# braids_v50.net
KiCad netlist of a schematic drawn in EAGLE
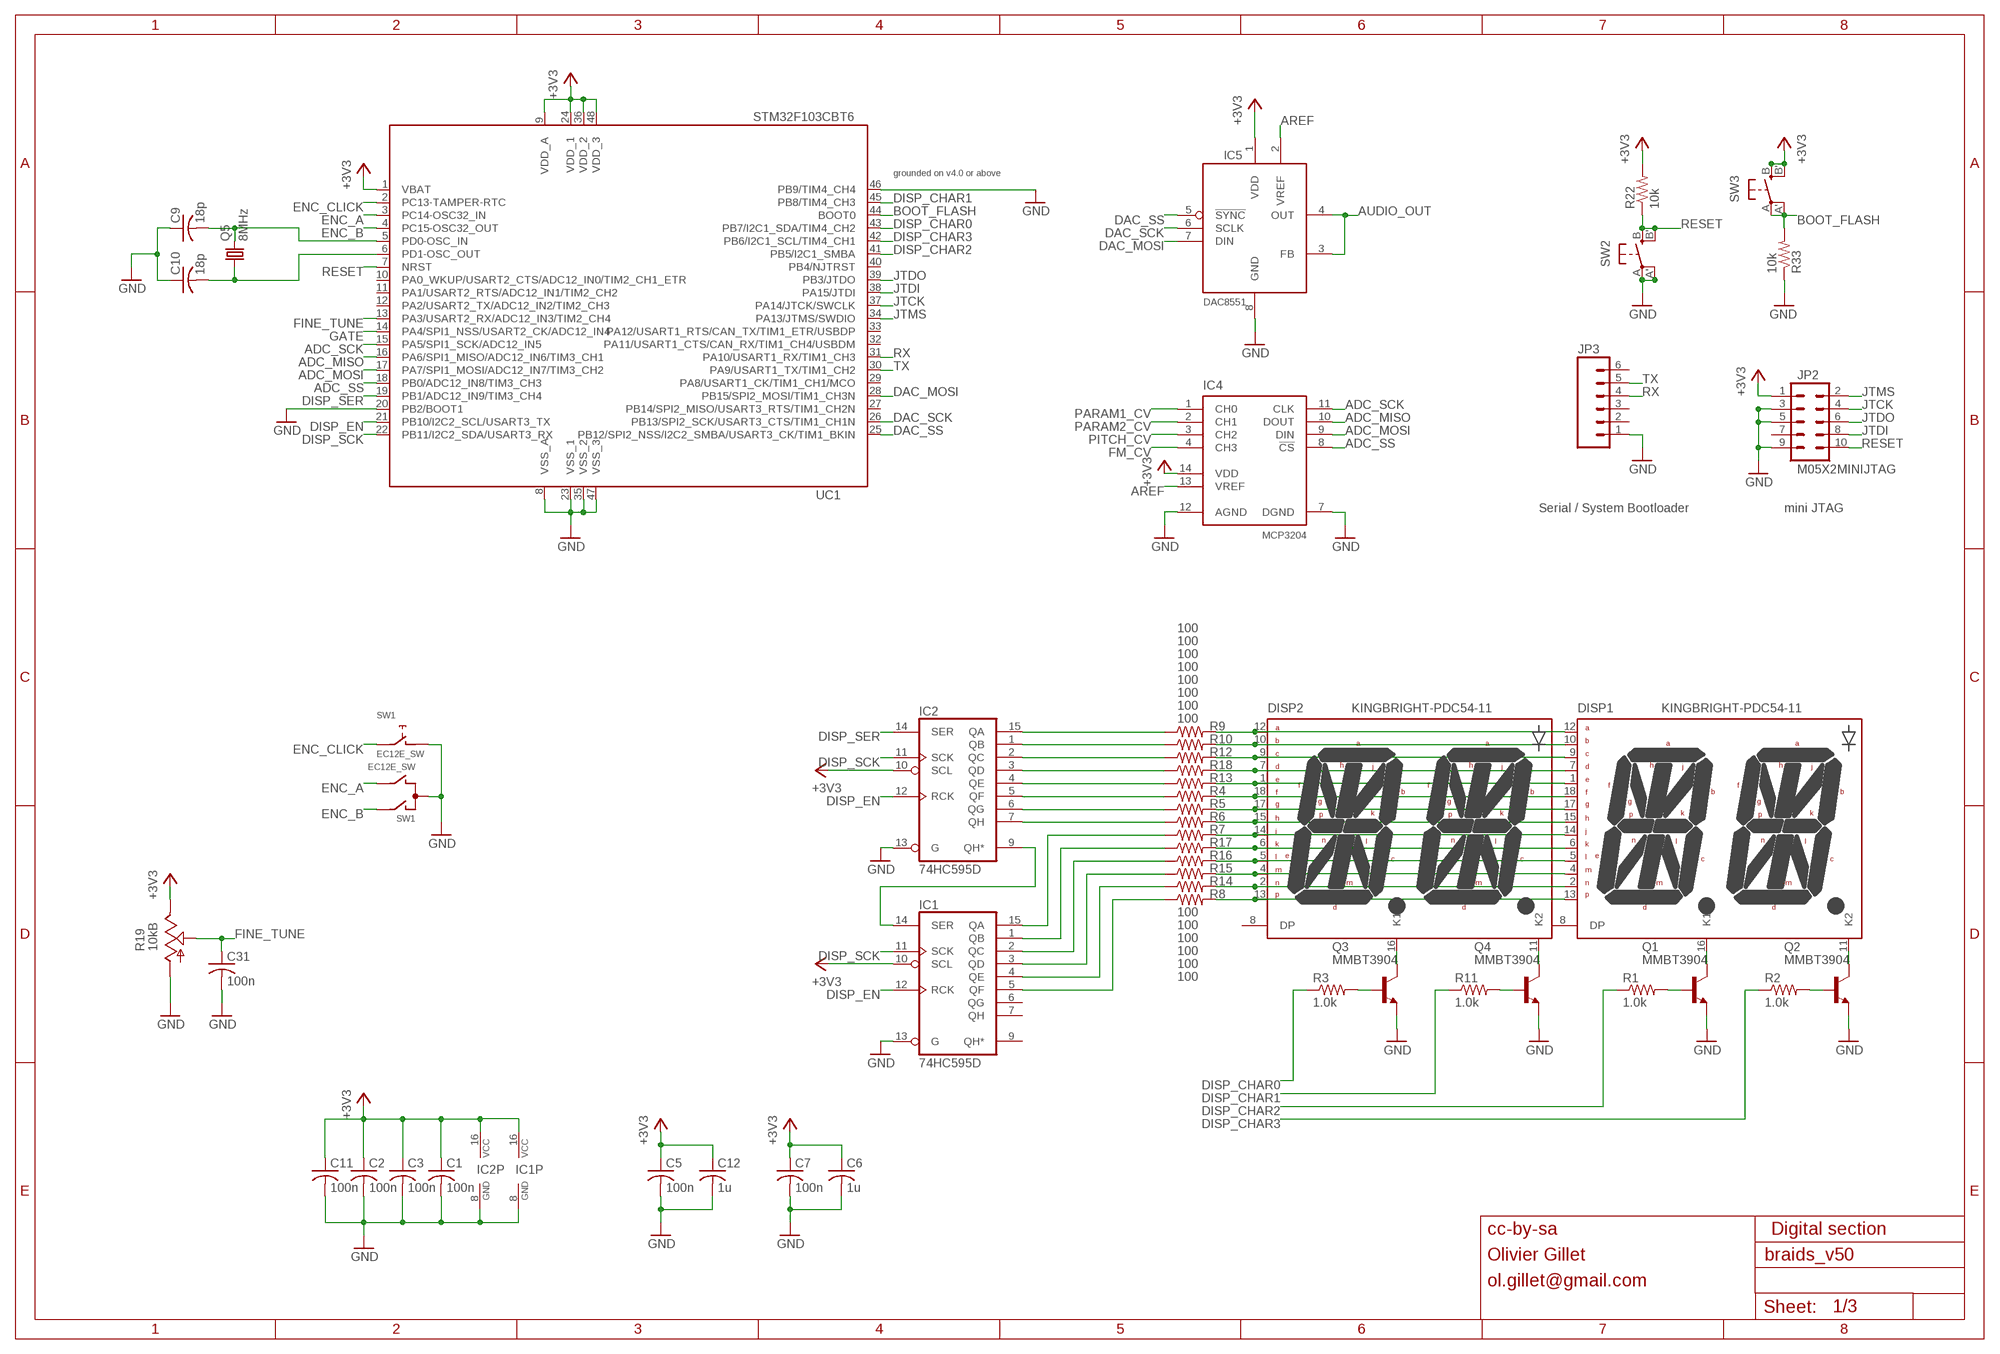
[diagram p0: schematic, sheet 1]
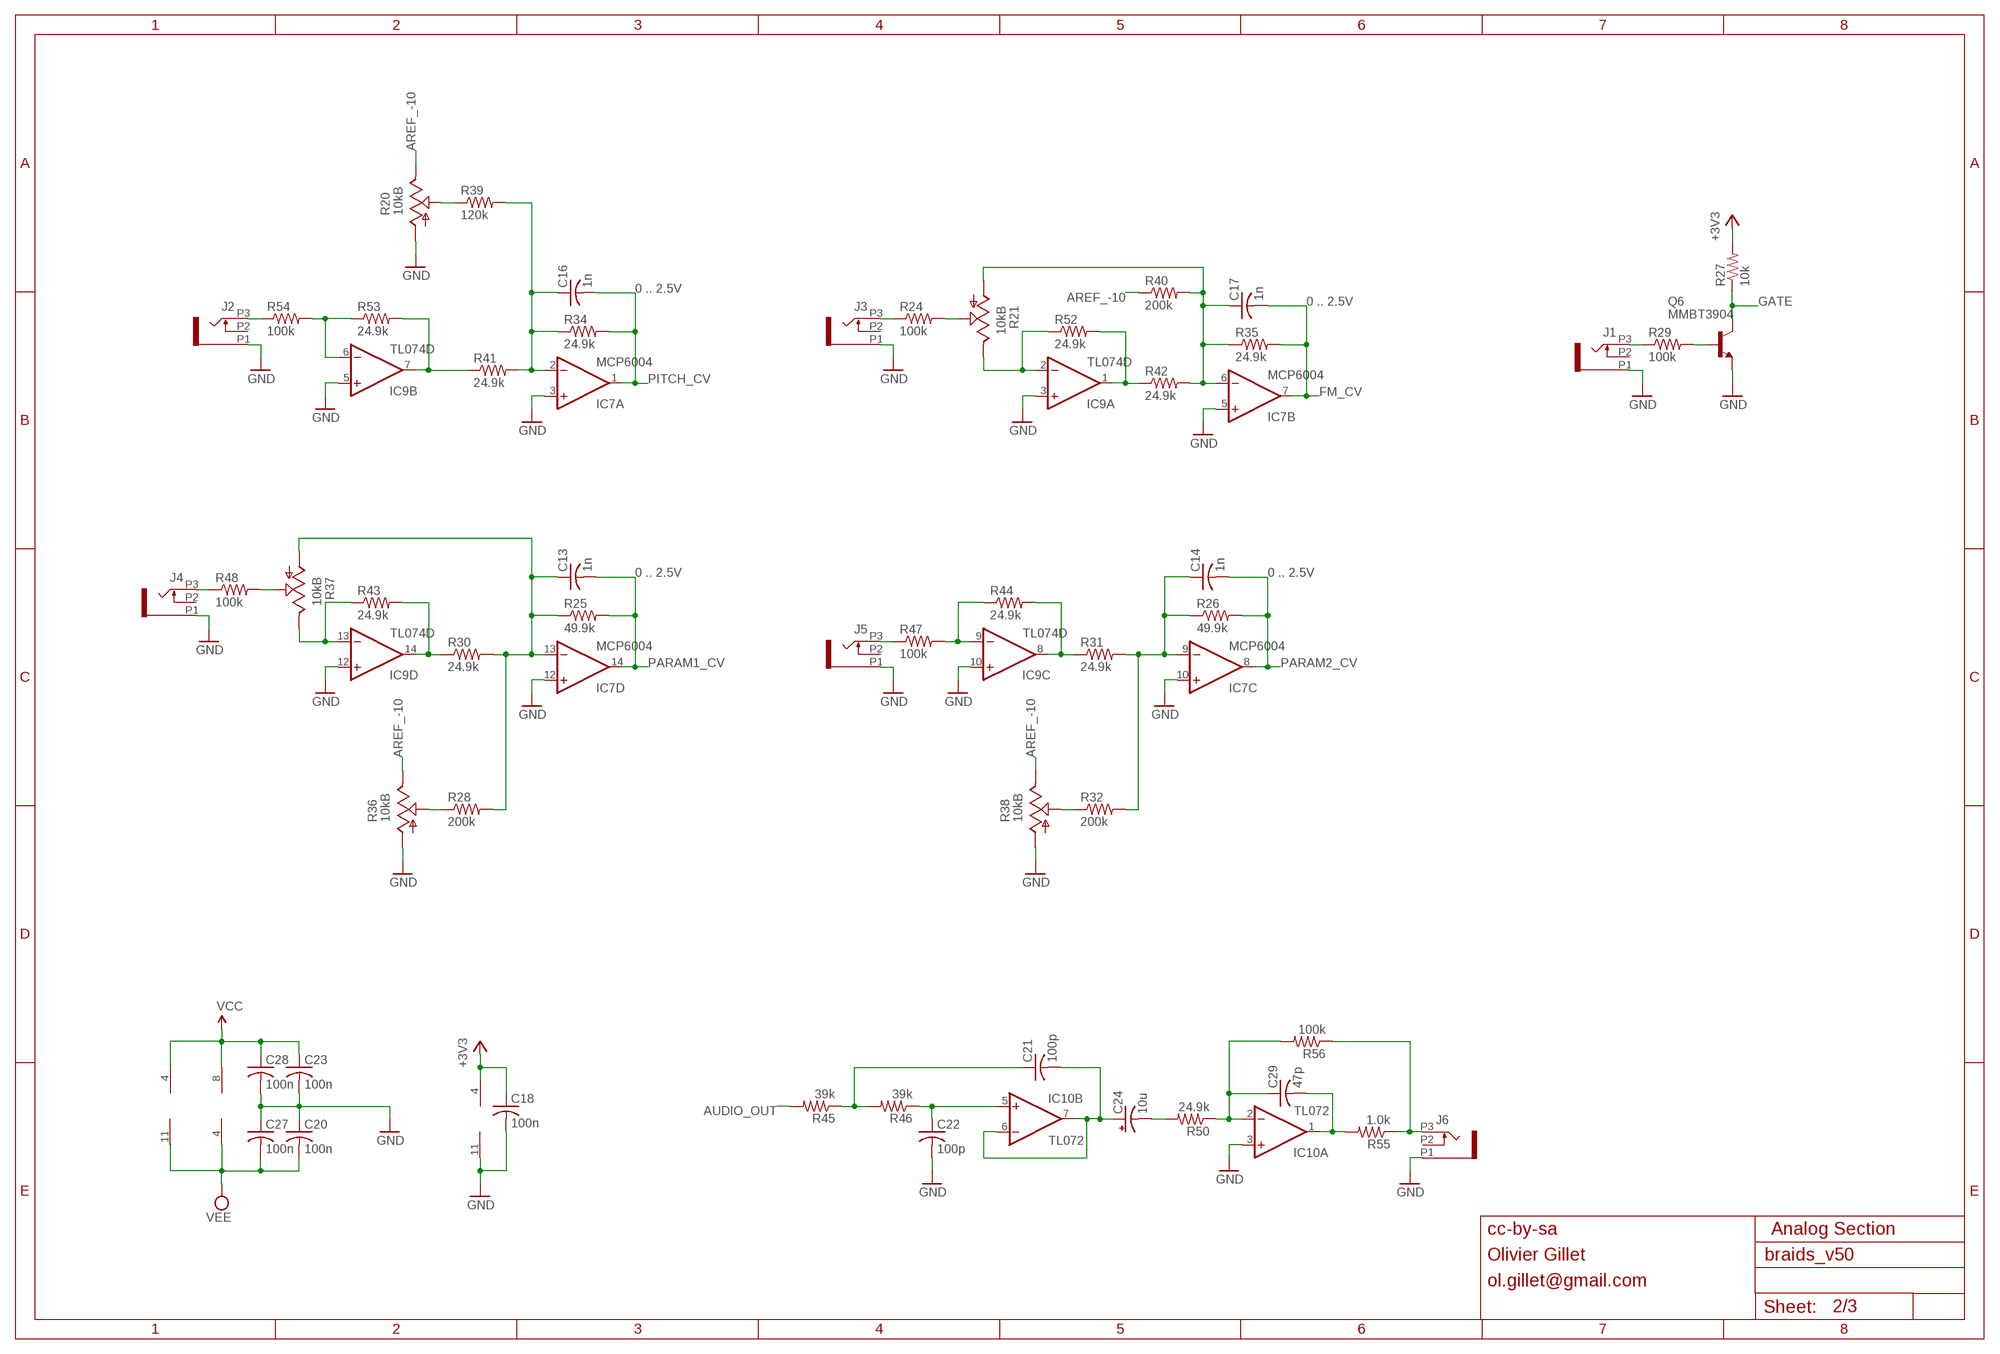
[diagram p1: schematic, sheet 2]
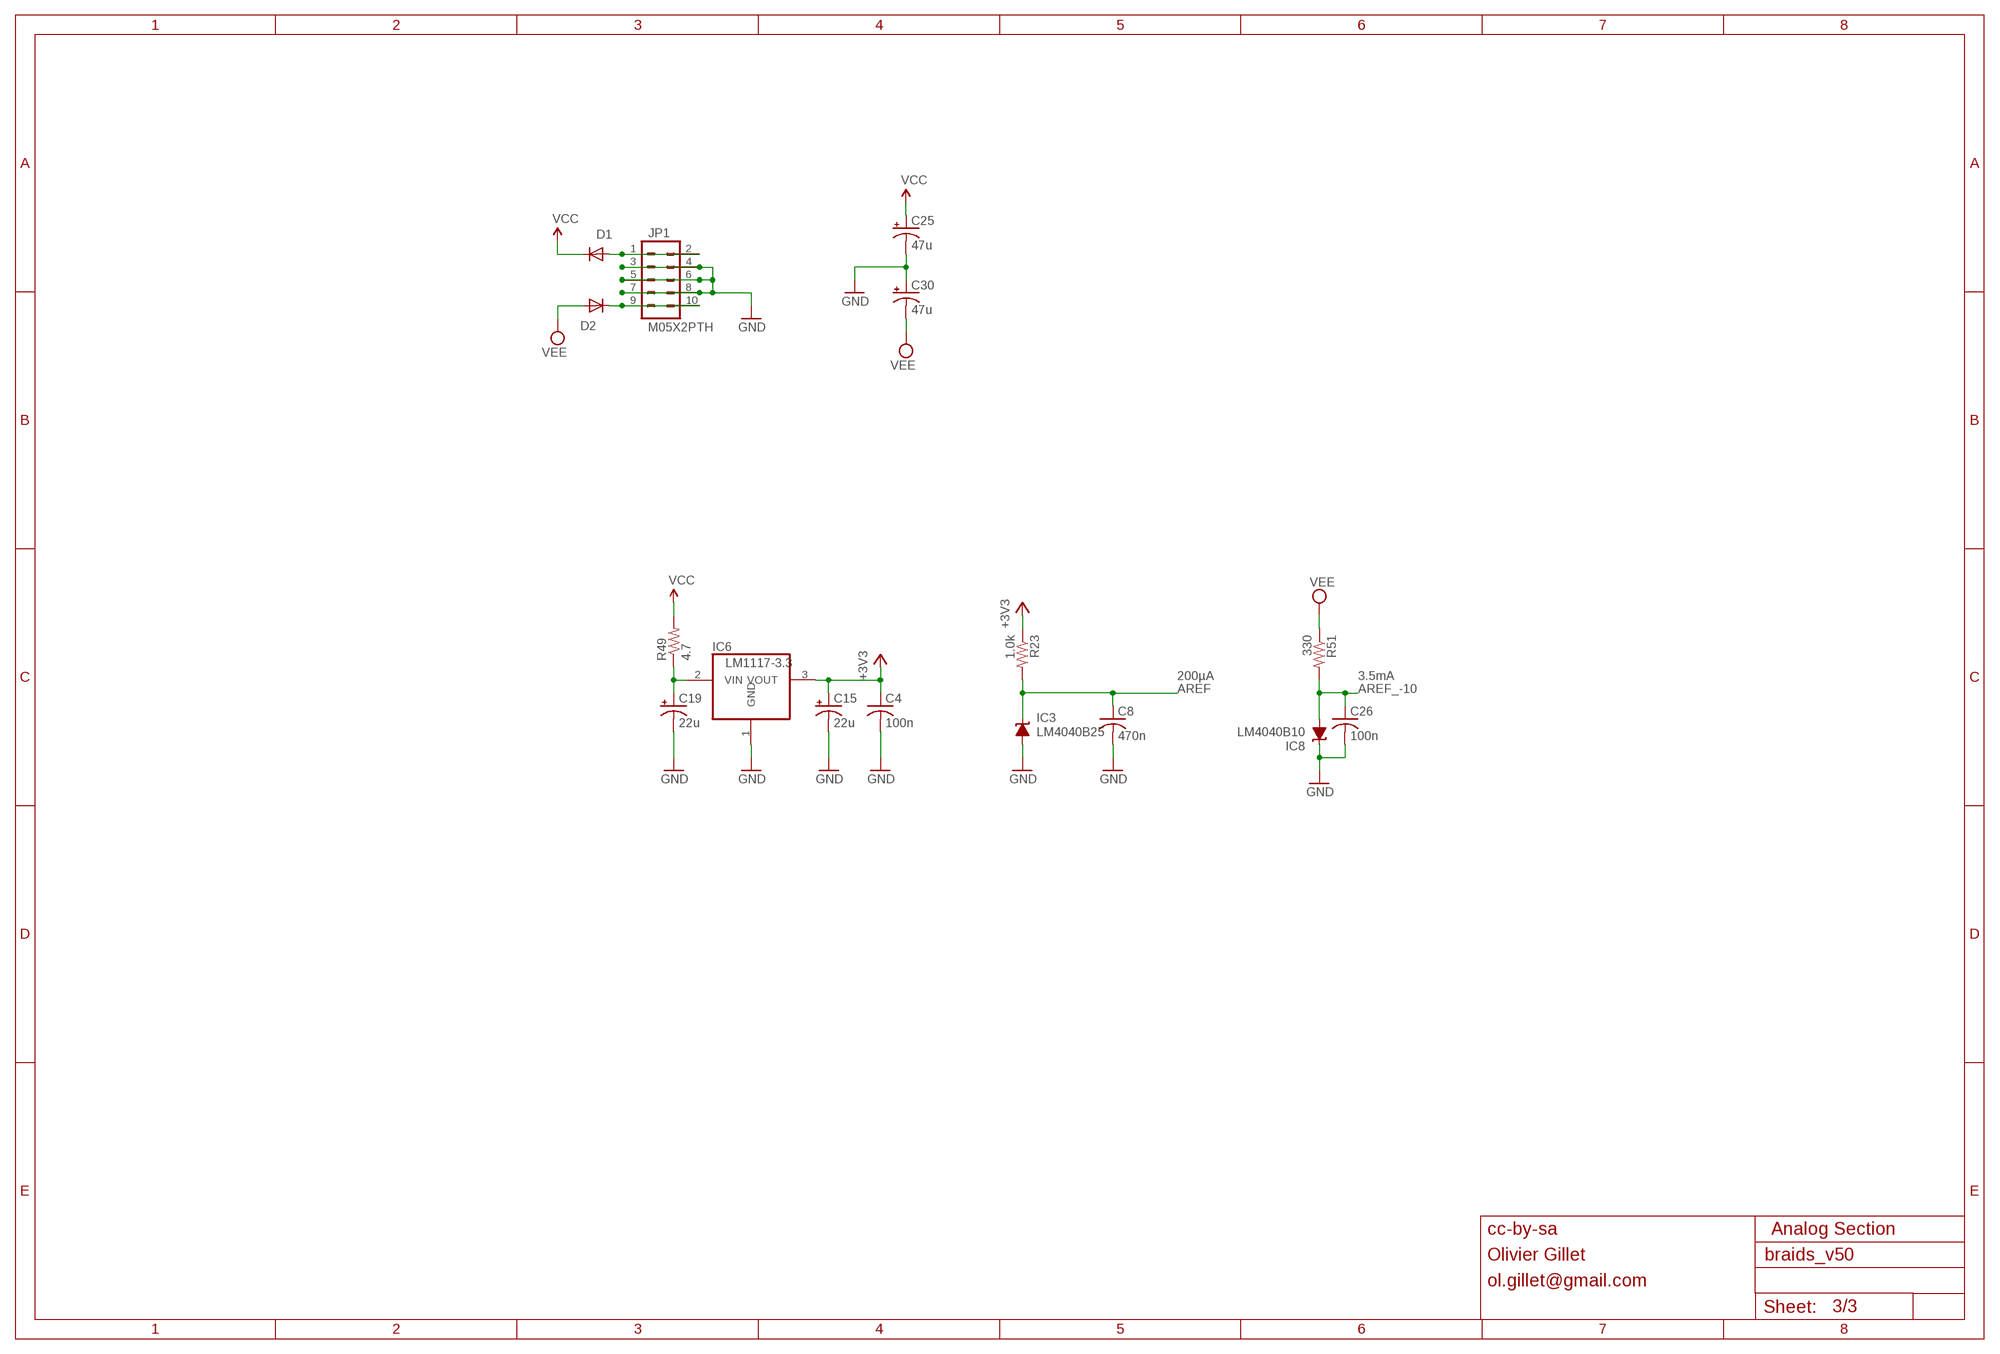
[diagram p2: schematic, sheet 3]

(export (version "E")
  (design (tool "Eeschema 10.0.6"))
  (components
    (comp (ref "C4")
      (value "100n")
      (footprint "eagle-import:C0603")
      (libsource (lib "eagle-import") (part "C-USC0603"))
    )
    (comp (ref "C8")
      (value "470n")
      (footprint "eagle-import:C0603")
      (libsource (lib "eagle-import") (part "C-USC0603"))
    )
    (comp (ref "C15")
      (value "22u")
      (footprint "eagle-import:PANASONIC_C")
      (libsource (lib "eagle-import") (part "CPOL-USC"))
    )
    (comp (ref "C19")
      (value "22u")
      (footprint "eagle-import:PANASONIC_C")
      (libsource (lib "eagle-import") (part "CPOL-USC"))
    )
    (comp (ref "C25")
      (value "47u")
      (footprint "eagle-import:PANASONIC_D")
      (libsource (lib "eagle-import") (part "CPOL-USD"))
    )
    (comp (ref "C26")
      (value "100n")
      (footprint "eagle-import:C0603")
      (libsource (lib "eagle-import") (part "C-USC0603"))
    )
    (comp (ref "C30")
      (value "47u")
      (footprint "eagle-import:PANASONIC_D")
      (libsource (lib "eagle-import") (part "CPOL-USD"))
    )
    (comp (ref "D1")
      (value "1N5819HW")
      (footprint "eagle-import:SOD123")
      (libsource (lib "eagle-import") (part "DIODE-SOD123"))
    )
    (comp (ref "D2")
      (value "1N5819HW")
      (footprint "eagle-import:SOD123")
      (libsource (lib "eagle-import") (part "DIODE-SOD123"))
    )
    (comp (ref "IC3")
      (value "LM4040B25")
      (footprint "eagle-import:DBZ_R-PDSO-G3")
      (libsource (lib "eagle-import") (part "LM4041DBZB12"))
    )
    (comp (ref "IC6")
      (value "LM1117-3.3")
      (footprint "eagle-import:TO252")
      (libsource (lib "eagle-import") (part "REG1117T"))
    )
    (comp (ref "IC8")
      (value "LM4040B10")
      (footprint "eagle-import:DBZ_R-PDSO-G3")
      (libsource (lib "eagle-import") (part "LM4041DBZB12"))
    )
    (comp (ref "JP1")
      (value "M05X2PTH")
      (footprint "eagle-import:AVR_ICSP")
      (libsource (lib "eagle-import") (part "M05X2PTH"))
    )
    (comp (ref "R23")
      (value "1.0k")
      (footprint "eagle-import:R0603")
      (libsource (lib "eagle-import") (part "R-US_R0603"))
    )
    (comp (ref "R49")
      (value "4.7")
      (footprint "eagle-import:R1206")
      (libsource (lib "eagle-import") (part "R-US_R1206"))
    )
    (comp (ref "R51")
      (value "330")
      (footprint "eagle-import:R0603")
      (libsource (lib "eagle-import") (part "R-US_R0603"))
    )
    (comp (ref "C13")
      (value "1n")
      (footprint "eagle-import:C0603")
      (libsource (lib "eagle-import") (part "C-USC0603"))
    )
    (comp (ref "C14")
      (value "1n")
      (footprint "eagle-import:C0603")
      (libsource (lib "eagle-import") (part "C-USC0603"))
    )
    (comp (ref "C16")
      (value "1n")
      (footprint "eagle-import:C0603")
      (libsource (lib "eagle-import") (part "C-USC0603"))
    )
    (comp (ref "C17")
      (value "1n")
      (footprint "eagle-import:C0603")
      (libsource (lib "eagle-import") (part "C-USC0603"))
    )
    (comp (ref "C18")
      (value "100n")
      (footprint "eagle-import:C0603")
      (libsource (lib "eagle-import") (part "C-USC0603"))
    )
    (comp (ref "C20")
      (value "100n")
      (footprint "eagle-import:C0603")
      (libsource (lib "eagle-import") (part "C-USC0603"))
    )
    (comp (ref "C21")
      (value "100p")
      (footprint "eagle-import:C0603")
      (libsource (lib "eagle-import") (part "C-USC0603"))
    )
    (comp (ref "C22")
      (value "100p")
      (footprint "eagle-import:C0603")
      (libsource (lib "eagle-import") (part "C-USC0603"))
    )
    (comp (ref "C23")
      (value "100n")
      (footprint "eagle-import:C0603")
      (libsource (lib "eagle-import") (part "C-USC0603"))
    )
    (comp (ref "C24")
      (value "10u")
      (footprint "eagle-import:PANASONIC_B")
      (libsource (lib "eagle-import") (part "CPOL-USB"))
    )
    (comp (ref "C27")
      (value "100n")
      (footprint "eagle-import:C0603")
      (libsource (lib "eagle-import") (part "C-USC0603"))
    )
    (comp (ref "C28")
      (value "100n")
      (footprint "eagle-import:C0603")
      (libsource (lib "eagle-import") (part "C-USC0603"))
    )
    (comp (ref "C29")
      (value "47p")
      (footprint "eagle-import:C0603")
      (libsource (lib "eagle-import") (part "C-USC0603"))
    )
    (comp (ref "IC7")
      (value "MCP6004")
      (footprint "eagle-import:SO14")
      (libsource (lib "eagle-import") (part "TL074D"))
    )
    (comp (ref "IC9")
      (value "TL074D")
      (footprint "eagle-import:SO14")
      (libsource (lib "eagle-import") (part "TL074D"))
    )
    (comp (ref "IC10")
      (value "TL072")
      (footprint "eagle-import:SO08")
      (libsource (lib "eagle-import") (part "TL072D"))
    )
    (comp (ref "J1")
      (value "PJ301_THONKICONN6")
      (footprint "eagle-import:WQP_PJ_301M6")
      (libsource (lib "eagle-import") (part "PJ301_THONKICONN6"))
    )
    (comp (ref "J2")
      (value "PJ301_THONKICONN6")
      (footprint "eagle-import:WQP_PJ_301M6")
      (libsource (lib "eagle-import") (part "PJ301_THONKICONN6"))
    )
    (comp (ref "J3")
      (value "PJ301_THONKICONN6")
      (footprint "eagle-import:WQP_PJ_301M6")
      (libsource (lib "eagle-import") (part "PJ301_THONKICONN6"))
    )
    (comp (ref "J4")
      (value "PJ301_THONKICONN6")
      (footprint "eagle-import:WQP_PJ_301M6")
      (libsource (lib "eagle-import") (part "PJ301_THONKICONN6"))
    )
    (comp (ref "J5")
      (value "PJ301_THONKICONN6")
      (footprint "eagle-import:WQP_PJ_301M6")
      (libsource (lib "eagle-import") (part "PJ301_THONKICONN6"))
    )
    (comp (ref "J6")
      (value "PJ301_THONKICONN6")
      (footprint "eagle-import:WQP_PJ_301M6")
      (libsource (lib "eagle-import") (part "PJ301_THONKICONN6"))
    )
    (comp (ref "Q6")
      (value "MMBT3904")
      (footprint "eagle-import:SOT23-BEC")
      (libsource (lib "eagle-import") (part "-NPN-SOT23-BECMMBT3904LT1"))
    )
    (comp (ref "R20")
      (value "10kB")
      (footprint "eagle-import:ALPS_POT_VERTICAL_PS")
      (libsource (lib "eagle-import") (part "POT_USVERTICAL_PS"))
    )
    (comp (ref "R21")
      (value "10kB")
      (footprint "eagle-import:ALPS_POT_VERTICAL_PS")
      (libsource (lib "eagle-import") (part "POT_USVERTICAL_PS"))
    )
    (comp (ref "R24")
      (value "100k")
      (footprint "eagle-import:R0603")
      (libsource (lib "eagle-import") (part "R-US_R0603"))
    )
    (comp (ref "R25")
      (value "49.9k")
      (footprint "eagle-import:R0603")
      (libsource (lib "eagle-import") (part "R-US_R0603"))
    )
    (comp (ref "R26")
      (value "49.9k")
      (footprint "eagle-import:R0603")
      (libsource (lib "eagle-import") (part "R-US_R0603"))
    )
    (comp (ref "R27")
      (value "10k")
      (footprint "eagle-import:R0603")
      (libsource (lib "eagle-import") (part "R-US_R0603"))
    )
    (comp (ref "R28")
      (value "200k")
      (footprint "eagle-import:R0603")
      (libsource (lib "eagle-import") (part "R-US_R0603"))
    )
    (comp (ref "R29")
      (value "100k")
      (footprint "eagle-import:R0603")
      (libsource (lib "eagle-import") (part "R-US_R0603"))
    )
    (comp (ref "R30")
      (value "24.9k")
      (footprint "eagle-import:R0603")
      (libsource (lib "eagle-import") (part "R-US_R0603"))
    )
    (comp (ref "R31")
      (value "24.9k")
      (footprint "eagle-import:R0603")
      (libsource (lib "eagle-import") (part "R-US_R0603"))
    )
    (comp (ref "R32")
      (value "200k")
      (footprint "eagle-import:R0603")
      (libsource (lib "eagle-import") (part "R-US_R0603"))
    )
    (comp (ref "R34")
      (value "24.9k")
      (footprint "eagle-import:R0603")
      (libsource (lib "eagle-import") (part "R-US_R0603"))
    )
    (comp (ref "R35")
      (value "24.9k")
      (footprint "eagle-import:R0603")
      (libsource (lib "eagle-import") (part "R-US_R0603"))
    )
    (comp (ref "R36")
      (value "10kB")
      (footprint "eagle-import:ALPS_POT_VERTICAL_PS")
      (libsource (lib "eagle-import") (part "POT_USVERTICAL_PS"))
    )
    (comp (ref "R37")
      (value "10kB")
      (footprint "eagle-import:ALPS_POT_VERTICAL_PS")
      (libsource (lib "eagle-import") (part "POT_USVERTICAL_PS"))
    )
    (comp (ref "R38")
      (value "10kB")
      (footprint "eagle-import:ALPS_POT_VERTICAL_PS")
      (libsource (lib "eagle-import") (part "POT_USVERTICAL_PS"))
    )
    (comp (ref "R39")
      (value "120k")
      (footprint "eagle-import:R0603")
      (libsource (lib "eagle-import") (part "R-US_R0603"))
    )
    (comp (ref "R40")
      (value "200k")
      (footprint "eagle-import:R0603")
      (libsource (lib "eagle-import") (part "R-US_R0603"))
    )
    (comp (ref "R41")
      (value "24.9k")
      (footprint "eagle-import:R0603")
      (libsource (lib "eagle-import") (part "R-US_R0603"))
    )
    (comp (ref "R42")
      (value "24.9k")
      (footprint "eagle-import:R0603")
      (libsource (lib "eagle-import") (part "R-US_R0603"))
    )
    (comp (ref "R43")
      (value "24.9k")
      (footprint "eagle-import:R0603")
      (libsource (lib "eagle-import") (part "R-US_R0603"))
    )
    (comp (ref "R44")
      (value "24.9k")
      (footprint "eagle-import:R0603")
      (libsource (lib "eagle-import") (part "R-US_R0603"))
    )
    (comp (ref "R45")
      (value "39k")
      (footprint "eagle-import:R0603")
      (libsource (lib "eagle-import") (part "R-US_R0603"))
    )
    (comp (ref "R46")
      (value "39k")
      (footprint "eagle-import:R0603")
      (libsource (lib "eagle-import") (part "R-US_R0603"))
    )
    (comp (ref "R47")
      (value "100k")
      (footprint "eagle-import:R0603")
      (libsource (lib "eagle-import") (part "R-US_R0603"))
    )
    (comp (ref "R48")
      (value "100k")
      (footprint "eagle-import:R0603")
      (libsource (lib "eagle-import") (part "R-US_R0603"))
    )
    (comp (ref "R50")
      (value "24.9k")
      (footprint "eagle-import:R0603")
      (libsource (lib "eagle-import") (part "R-US_R0603"))
    )
    (comp (ref "R52")
      (value "24.9k")
      (footprint "eagle-import:R0603")
      (libsource (lib "eagle-import") (part "R-US_R0603"))
    )
    (comp (ref "R53")
      (value "24.9k")
      (footprint "eagle-import:R0603")
      (libsource (lib "eagle-import") (part "R-US_R0603"))
    )
    (comp (ref "R54")
      (value "100k")
      (footprint "eagle-import:R0603")
      (libsource (lib "eagle-import") (part "R-US_R0603"))
    )
    (comp (ref "R55")
      (value "1.0k")
      (footprint "eagle-import:R0603")
      (libsource (lib "eagle-import") (part "R-US_R0603"))
    )
    (comp (ref "R56")
      (value "100k")
      (footprint "eagle-import:R0603")
      (libsource (lib "eagle-import") (part "R-US_R0603"))
    )
    (comp (ref "C1")
      (value "100n")
      (footprint "eagle-import:C0603")
      (libsource (lib "eagle-import") (part "C-USC0603"))
    )
    (comp (ref "C2")
      (value "100n")
      (footprint "eagle-import:C0603")
      (libsource (lib "eagle-import") (part "C-USC0603"))
    )
    (comp (ref "C3")
      (value "100n")
      (footprint "eagle-import:C0603")
      (libsource (lib "eagle-import") (part "C-USC0603"))
    )
    (comp (ref "C5")
      (value "100n")
      (footprint "eagle-import:C0603")
      (libsource (lib "eagle-import") (part "C-USC0603"))
    )
    (comp (ref "C6")
      (value "1u")
      (footprint "eagle-import:C0603")
      (libsource (lib "eagle-import") (part "C-USC0603"))
    )
    (comp (ref "C7")
      (value "100n")
      (footprint "eagle-import:C0603")
      (libsource (lib "eagle-import") (part "C-USC0603"))
    )
    (comp (ref "C9")
      (value "18p")
      (footprint "eagle-import:C0603")
      (libsource (lib "eagle-import") (part "C-USC0603"))
    )
    (comp (ref "C10")
      (value "18p")
      (footprint "eagle-import:C0603")
      (libsource (lib "eagle-import") (part "C-USC0603"))
    )
    (comp (ref "C11")
      (value "100n")
      (footprint "eagle-import:C0603")
      (libsource (lib "eagle-import") (part "C-USC0603"))
    )
    (comp (ref "C12")
      (value "1u")
      (footprint "eagle-import:C0603")
      (libsource (lib "eagle-import") (part "C-USC0603"))
    )
    (comp (ref "C31")
      (value "100n")
      (footprint "eagle-import:C0603")
      (libsource (lib "eagle-import") (part "C-USC0603"))
    )
    (comp (ref "DISP1")
      (value "KINGBRIGHT-PDC54-11")
      (footprint "eagle-import:PDC54")
      (libsource (lib "eagle-import") (part "KINGBRIGHT-PDC54-11"))
    )
    (comp (ref "DISP2")
      (value "KINGBRIGHT-PDC54-11")
      (footprint "eagle-import:PDC54")
      (libsource (lib "eagle-import") (part "KINGBRIGHT-PDC54-11"))
    )
    (comp (ref "IC1")
      (value "74HC595D")
      (footprint "eagle-import:SO16")
      (libsource (lib "eagle-import") (part "74595DHC"))
    )
    (comp (ref "IC2")
      (value "74HC595D")
      (footprint "eagle-import:SO16")
      (libsource (lib "eagle-import") (part "74595DHC"))
    )
    (comp (ref "IC4")
      (value "MCP3204")
      (footprint "eagle-import:SO14")
      (libsource (lib "eagle-import") (part "MCP3302"))
    )
    (comp (ref "IC5")
      (value "DAC8551")
      (footprint "eagle-import:MSOP-8")
      (libsource (lib "eagle-import") (part "DAC855X"))
    )
    (comp (ref "JP2")
      (value "M05X2MINIJTAG")
      (footprint "eagle-import:2X5-1.27")
      (libsource (lib "eagle-import") (part "M05X2MINIJTAG"))
    )
    (comp (ref "JP3")
      (value "M06SIP")
      (footprint "eagle-import:1X06")
      (libsource (lib "eagle-import") (part "M06SIP"))
    )
    (comp (ref "Q1")
      (value "MMBT3904")
      (footprint "eagle-import:SOT23-BEC")
      (libsource (lib "eagle-import") (part "-NPN-SOT23-BECMMBT3904LT1"))
    )
    (comp (ref "Q2")
      (value "MMBT3904")
      (footprint "eagle-import:SOT23-BEC")
      (libsource (lib "eagle-import") (part "-NPN-SOT23-BECMMBT3904LT1"))
    )
    (comp (ref "Q3")
      (value "MMBT3904")
      (footprint "eagle-import:SOT23-BEC")
      (libsource (lib "eagle-import") (part "-NPN-SOT23-BECMMBT3904LT1"))
    )
    (comp (ref "Q4")
      (value "MMBT3904")
      (footprint "eagle-import:SOT23-BEC")
      (libsource (lib "eagle-import") (part "-NPN-SOT23-BECMMBT3904LT1"))
    )
    (comp (ref "Q5")
      (value "8MHz")
      (footprint "eagle-import:HC49UP")
      (libsource (lib "eagle-import") (part "CRYSTALHC49UP"))
    )
    (comp (ref "R1")
      (value "1.0k")
      (footprint "eagle-import:R0603")
      (libsource (lib "eagle-import") (part "R-US_R0603"))
    )
    (comp (ref "R2")
      (value "1.0k")
      (footprint "eagle-import:R0603")
      (libsource (lib "eagle-import") (part "R-US_R0603"))
    )
    (comp (ref "R3")
      (value "1.0k")
      (footprint "eagle-import:R0603")
      (libsource (lib "eagle-import") (part "R-US_R0603"))
    )
    (comp (ref "R4")
      (value "100")
      (footprint "eagle-import:R0603")
      (libsource (lib "eagle-import") (part "R-US_R0603"))
    )
    (comp (ref "R5")
      (value "100")
      (footprint "eagle-import:R0603")
      (libsource (lib "eagle-import") (part "R-US_R0603"))
    )
    (comp (ref "R6")
      (value "100")
      (footprint "eagle-import:R0603")
      (libsource (lib "eagle-import") (part "R-US_R0603"))
    )
    (comp (ref "R7")
      (value "100")
      (footprint "eagle-import:R0603")
      (libsource (lib "eagle-import") (part "R-US_R0603"))
    )
    (comp (ref "R8")
      (value "100")
      (footprint "eagle-import:R0603")
      (libsource (lib "eagle-import") (part "R-US_R0603"))
    )
    (comp (ref "R9")
      (value "100")
      (footprint "eagle-import:R0603")
      (libsource (lib "eagle-import") (part "R-US_R0603"))
    )
    (comp (ref "R10")
      (value "100")
      (footprint "eagle-import:R0603")
      (libsource (lib "eagle-import") (part "R-US_R0603"))
    )
    (comp (ref "R11")
      (value "1.0k")
      (footprint "eagle-import:R0603")
      (libsource (lib "eagle-import") (part "R-US_R0603"))
    )
    (comp (ref "R12")
      (value "100")
      (footprint "eagle-import:R0603")
      (libsource (lib "eagle-import") (part "R-US_R0603"))
    )
    (comp (ref "R13")
      (value "100")
      (footprint "eagle-import:R0603")
      (libsource (lib "eagle-import") (part "R-US_R0603"))
    )
    (comp (ref "R14")
      (value "100")
      (footprint "eagle-import:R0603")
      (libsource (lib "eagle-import") (part "R-US_R0603"))
    )
    (comp (ref "R15")
      (value "100")
      (footprint "eagle-import:R0603")
      (libsource (lib "eagle-import") (part "R-US_R0603"))
    )
    (comp (ref "R16")
      (value "100")
      (footprint "eagle-import:R0603")
      (libsource (lib "eagle-import") (part "R-US_R0603"))
    )
    (comp (ref "R17")
      (value "100")
      (footprint "eagle-import:R0603")
      (libsource (lib "eagle-import") (part "R-US_R0603"))
    )
    (comp (ref "R18")
      (value "100")
      (footprint "eagle-import:R0603")
      (libsource (lib "eagle-import") (part "R-US_R0603"))
    )
    (comp (ref "R19")
      (value "10kB")
      (footprint "eagle-import:ALPS_POT_VERTICAL_PS")
      (libsource (lib "eagle-import") (part "POT_USVERTICAL_PS"))
    )
    (comp (ref "R22")
      (value "10k")
      (footprint "eagle-import:R0603")
      (libsource (lib "eagle-import") (part "R-US_R0603"))
    )
    (comp (ref "R33")
      (value "10k")
      (footprint "eagle-import:R0603")
      (libsource (lib "eagle-import") (part "R-US_R0603"))
    )
    (comp (ref "SW1")
      (value "EC12E_SW")
      (footprint "eagle-import:ALPS_EC12E_SW")
      (libsource (lib "eagle-import") (part "EC12E_SW"))
    )
    (comp (ref "SW2")
      (value "EVQQ2")
      (footprint "eagle-import:EVQ-Q2")
      (libsource (lib "eagle-import") (part "EVQQ2"))
    )
    (comp (ref "SW3")
      (value "EVQQ2")
      (footprint "eagle-import:EVQ-Q2")
      (libsource (lib "eagle-import") (part "EVQQ2"))
    )
    (comp (ref "UC1")
      (value "STM32F103CBT6")
      (footprint "eagle-import:LQFP48")
      (libsource (lib "eagle-import") (part "STM32F103CB"))
    )
  )
  (nets
    (net (code "1") (name "+3V3") (class "Default")
      (node (ref "C1") (pin "1") (pinfunction "1_1") (pintype "passive"))
      (node (ref "C11") (pin "1") (pinfunction "1_1") (pintype "passive"))
      (node (ref "C12") (pin "1") (pinfunction "1_1") (pintype "passive"))
      (node (ref "C15") (pin "+") (pinfunction "+_+") (pintype "passive"))
      (node (ref "C18") (pin "1") (pinfunction "1_1") (pintype "passive"))
      (node (ref "C2") (pin "1") (pinfunction "1_1") (pintype "passive"))
      (node (ref "C3") (pin "1") (pinfunction "1_1") (pintype "passive"))
      (node (ref "C4") (pin "1") (pinfunction "1_1") (pintype "passive"))
      (node (ref "C5") (pin "1") (pinfunction "1_1") (pintype "passive"))
      (node (ref "C6") (pin "1") (pinfunction "1_1") (pintype "passive"))
      (node (ref "C7") (pin "1") (pinfunction "1_1") (pintype "passive"))
      (node (ref "IC1") (pin "10") (pinfunction "SCL_10") (pintype "input"))
      (node (ref "IC1") (pin "16") (pinfunction "VCC_16") (pintype "power_in"))
      (node (ref "IC2") (pin "10") (pinfunction "SCL_10") (pintype "input"))
      (node (ref "IC2") (pin "16") (pinfunction "VCC_16") (pintype "power_in"))
      (node (ref "IC4") (pin "14") (pinfunction "VDD_14") (pintype "bidirectional"))
      (node (ref "IC5") (pin "1") (pinfunction "VDD_1") (pintype "power_in"))
      (node (ref "IC6") (pin "3") (pinfunction "VOUT_3") (pintype "output"))
      (node (ref "IC7") (pin "4") (pinfunction "V+_4") (pintype "power_in"))
      (node (ref "JP2") (pin "1") (pinfunction "1_1") (pintype "passive"))
      (node (ref "R19") (pin "P$1") (pinfunction "E_P$1") (pintype "passive"))
      (node (ref "R22") (pin "2") (pinfunction "2_2") (pintype "passive"))
      (node (ref "R23") (pin "1") (pinfunction "1_1") (pintype "passive"))
      (node (ref "R27") (pin "2") (pinfunction "2_2") (pintype "passive"))
      (node (ref "SW3") (pin "B") (pinfunction "S_B") (pintype "passive"))
      (node (ref "SW3") (pin "B'") (pinfunction "S1_B'") (pintype "passive"))
      (node (ref "UC1") (pin "1") (pinfunction "VBAT_1") (pintype "power_in"))
      (node (ref "UC1") (pin "24") (pinfunction "VDD_1_24") (pintype "power_in"))
      (node (ref "UC1") (pin "36") (pinfunction "VDD_2_36") (pintype "power_in"))
      (node (ref "UC1") (pin "48") (pinfunction "VDD_3_48") (pintype "power_in"))
      (node (ref "UC1") (pin "9") (pinfunction "VDD_A_9") (pintype "power_in"))
    )
    (net (code "2") (name "ADC_MISO") (class "Default")
      (node (ref "IC4") (pin "10") (pinfunction "DOUT_10") (pintype "bidirectional"))
      (node (ref "UC1") (pin "16") (pinfunction "PA6/SPI1_MISO/ADC12_IN6/TIM3_CH1_16") (pintype "bidirectional"))
    )
    (net (code "3") (name "ADC_MOSI") (class "Default")
      (node (ref "IC4") (pin "9") (pinfunction "DIN_9") (pintype "bidirectional"))
      (node (ref "UC1") (pin "17") (pinfunction "PA7/SPI1_MOSI/ADC12_IN7/TIM3_CH2_17") (pintype "bidirectional"))
    )
    (net (code "4") (name "ADC_SCK") (class "Default")
      (node (ref "IC4") (pin "11") (pinfunction "CLK_11") (pintype "bidirectional"))
      (node (ref "UC1") (pin "15") (pinfunction "PA5/SPI1_SCK/ADC12_IN5_15") (pintype "bidirectional"))
    )
    (net (code "5") (name "ADC_SS") (class "Default")
      (node (ref "IC4") (pin "8") (pinfunction "~{CS}_8") (pintype "bidirectional"))
      (node (ref "UC1") (pin "18") (pinfunction "PB0/ADC12_IN8/TIM3_CH3_18") (pintype "bidirectional"))
    )
    (net (code "6") (name "AREF") (class "Default")
      (node (ref "C8") (pin "1") (pinfunction "1_1") (pintype "passive"))
      (node (ref "IC3") (pin "1") (pinfunction "C_1") (pintype "passive"))
      (node (ref "IC4") (pin "13") (pinfunction "VREF_13") (pintype "bidirectional"))
      (node (ref "IC5") (pin "2") (pinfunction "VREF_2") (pintype "power_in"))
      (node (ref "R23") (pin "2") (pinfunction "2_2") (pintype "passive"))
    )
    (net (code "7") (name "AREF_-10") (class "Default")
      (node (ref "C26") (pin "1") (pinfunction "1_1") (pintype "passive"))
      (node (ref "IC8") (pin "2") (pinfunction "A_2") (pintype "passive"))
      (node (ref "R20") (pin "P$1") (pinfunction "E_P$1") (pintype "passive"))
      (node (ref "R36") (pin "P$1") (pinfunction "E_P$1") (pintype "passive"))
      (node (ref "R38") (pin "P$1") (pinfunction "E_P$1") (pintype "passive"))
      (node (ref "R40") (pin "1") (pinfunction "1_1") (pintype "passive"))
      (node (ref "R51") (pin "2") (pinfunction "2_2") (pintype "passive"))
    )
    (net (code "8") (name "AUDIO_OUT") (class "Default")
      (node (ref "IC5") (pin "3") (pinfunction "FB_3") (pintype "input"))
      (node (ref "IC5") (pin "4") (pinfunction "OUT_4") (pintype "output"))
      (node (ref "R45") (pin "2") (pinfunction "2_2") (pintype "passive"))
    )
    (net (code "9") (name "BOOT_FLASH") (class "Default")
      (node (ref "R33") (pin "2") (pinfunction "2_2") (pintype "passive"))
      (node (ref "SW3") (pin "A") (pinfunction "P_A") (pintype "passive"))
      (node (ref "SW3") (pin "A'") (pinfunction "P1_A'") (pintype "passive"))
      (node (ref "UC1") (pin "44") (pinfunction "BOOT0_44") (pintype "input"))
    )
    (net (code "10") (name "DAC_MOSI") (class "Default")
      (node (ref "IC5") (pin "7") (pinfunction "DIN_7") (pintype "bidirectional"))
      (node (ref "UC1") (pin "28") (pinfunction "PB15/SPI2_MOSI/TIM1_CH3N_28") (pintype "input"))
    )
    (net (code "11") (name "DAC_SCK") (class "Default")
      (node (ref "IC5") (pin "6") (pinfunction "SCLK_6") (pintype "bidirectional"))
      (node (ref "UC1") (pin "26") (pinfunction "PB13/SPI2_SCK/USART3_CTS/TIM1_CH1N_26") (pintype "input"))
    )
    (net (code "12") (name "DAC_SS") (class "Default")
      (node (ref "IC5") (pin "5") (pinfunction "~{SYNC}_5") (pintype "bidirectional"))
      (node (ref "UC1") (pin "25") (pinfunction "PB12/SPI2_NSS/I2C2_SMBA/USART3_CK/TIM1_BKIN_25") (pintype "input"))
    )
    (net (code "13") (name "DISP_CHAR0") (class "Default")
      (node (ref "R3") (pin "1") (pinfunction "1_1") (pintype "passive"))
      (node (ref "UC1") (pin "43") (pinfunction "PB7/I2C1_SDA/TIM4_CH2_43") (pintype "bidirectional"))
    )
    (net (code "14") (name "DISP_CHAR1") (class "Default")
      (node (ref "R11") (pin "1") (pinfunction "1_1") (pintype "passive"))
      (node (ref "UC1") (pin "45") (pinfunction "PB8/TIM4_CH3_45") (pintype "bidirectional"))
    )
    (net (code "15") (name "DISP_CHAR2") (class "Default")
      (node (ref "R1") (pin "1") (pinfunction "1_1") (pintype "passive"))
      (node (ref "UC1") (pin "41") (pinfunction "PB5/I2C1_SMBA_41") (pintype "input"))
    )
    (net (code "16") (name "DISP_CHAR3") (class "Default")
      (node (ref "R2") (pin "1") (pinfunction "1_1") (pintype "passive"))
      (node (ref "UC1") (pin "42") (pinfunction "PB6/I2C1_SCL/TIM4_CH1_42") (pintype "input"))
    )
    (net (code "17") (name "DISP_EN") (class "Default")
      (node (ref "IC1") (pin "12") (pinfunction "RCK_12") (pintype "input"))
      (node (ref "IC2") (pin "12") (pinfunction "RCK_12") (pintype "input"))
      (node (ref "UC1") (pin "21") (pinfunction "PB10/I2C2_SCL/USART3_TX_21") (pintype "input"))
    )
    (net (code "18") (name "DISP_SCK") (class "Default")
      (node (ref "IC1") (pin "11") (pinfunction "SCK_11") (pintype "input"))
      (node (ref "IC2") (pin "11") (pinfunction "SCK_11") (pintype "input"))
      (node (ref "UC1") (pin "22") (pinfunction "PB11/I2C2_SDA/USART3_RX_22") (pintype "input"))
    )
    (net (code "19") (name "DISP_SER") (class "Default")
      (node (ref "IC2") (pin "14") (pinfunction "SER_14") (pintype "input"))
      (node (ref "UC1") (pin "19") (pinfunction "PB1/ADC12_IN9/TIM3_CH4_19") (pintype "bidirectional"))
    )
    (net (code "20") (name "ENC_A") (class "Default")
      (node (ref "SW1") (pin "B") (pinfunction "B_B") (pintype "passive"))
      (node (ref "UC1") (pin "3") (pinfunction "PC14-OSC32_IN_3") (pintype "input"))
    )
    (net (code "21") (name "ENC_B") (class "Default")
      (node (ref "SW1") (pin "A") (pinfunction "A_A") (pintype "passive"))
      (node (ref "UC1") (pin "4") (pinfunction "PC15-OSC32_OUT_4") (pintype "input"))
    )
    (net (code "22") (name "ENC_CLICK") (class "Default")
      (node (ref "SW1") (pin "E") (pinfunction "2_E") (pintype "passive"))
      (node (ref "UC1") (pin "2") (pinfunction "PC13-TAMPER-RTC_2") (pintype "input"))
    )
    (net (code "23") (name "FINE_TUNE") (class "Default")
      (node (ref "C31") (pin "1") (pinfunction "1_1") (pintype "passive"))
      (node (ref "R19") (pin "P$2") (pinfunction "S_P$2") (pintype "passive"))
      (node (ref "UC1") (pin "13") (pinfunction "PA3/USART2_RX/ADC12_IN3/TIM2_CH4_13") (pintype "bidirectional"))
    )
    (net (code "24") (name "FM_CV") (class "Default")
      (node (ref "C17") (pin "2") (pinfunction "2_2") (pintype "passive"))
      (node (ref "IC4") (pin "4") (pinfunction "CH3_4") (pintype "bidirectional"))
      (node (ref "IC7") (pin "7") (pinfunction "OUT_7") (pintype "output"))
      (node (ref "R35") (pin "2") (pinfunction "2_2") (pintype "passive"))
    )
    (net (code "25") (name "GATE") (class "Default")
      (node (ref "Q6") (pin "C") (pinfunction "C_C") (pintype "passive"))
      (node (ref "R27") (pin "1") (pinfunction "1_1") (pintype "passive"))
      (node (ref "UC1") (pin "14") (pinfunction "PA4/SPI1_NSS/USART2_CK/ADC12_IN4_14") (pintype "bidirectional"))
    )
    (net (code "26") (name "GND") (class "Default")
      (node (ref "C1") (pin "2") (pinfunction "2_2") (pintype "passive"))
      (node (ref "C10") (pin "1") (pinfunction "1_1") (pintype "passive"))
      (node (ref "C11") (pin "2") (pinfunction "2_2") (pintype "passive"))
      (node (ref "C12") (pin "2") (pinfunction "2_2") (pintype "passive"))
      (node (ref "C15") (pin "-") (pinfunction "-_-") (pintype "passive"))
      (node (ref "C18") (pin "2") (pinfunction "2_2") (pintype "passive"))
      (node (ref "C19") (pin "-") (pinfunction "-_-") (pintype "passive"))
      (node (ref "C2") (pin "2") (pinfunction "2_2") (pintype "passive"))
      (node (ref "C20") (pin "1") (pinfunction "1_1") (pintype "passive"))
      (node (ref "C22") (pin "2") (pinfunction "2_2") (pintype "passive"))
      (node (ref "C23") (pin "2") (pinfunction "2_2") (pintype "passive"))
      (node (ref "C25") (pin "-") (pinfunction "-_-") (pintype "passive"))
      (node (ref "C26") (pin "2") (pinfunction "2_2") (pintype "passive"))
      (node (ref "C27") (pin "1") (pinfunction "1_1") (pintype "passive"))
      (node (ref "C28") (pin "2") (pinfunction "2_2") (pintype "passive"))
      (node (ref "C3") (pin "2") (pinfunction "2_2") (pintype "passive"))
      (node (ref "C30") (pin "+") (pinfunction "+_+") (pintype "passive"))
      (node (ref "C31") (pin "2") (pinfunction "2_2") (pintype "passive"))
      (node (ref "C4") (pin "2") (pinfunction "2_2") (pintype "passive"))
      (node (ref "C5") (pin "2") (pinfunction "2_2") (pintype "passive"))
      (node (ref "C6") (pin "2") (pinfunction "2_2") (pintype "passive"))
      (node (ref "C7") (pin "2") (pinfunction "2_2") (pintype "passive"))
      (node (ref "C8") (pin "2") (pinfunction "2_2") (pintype "passive"))
      (node (ref "C9") (pin "1") (pinfunction "1_1") (pintype "passive"))
      (node (ref "IC1") (pin "13") (pinfunction "G_13") (pintype "input"))
      (node (ref "IC1") (pin "8") (pinfunction "GND_8") (pintype "power_in"))
      (node (ref "IC10") (pin "3") (pinfunction "+IN_3") (pintype "input"))
      (node (ref "IC2") (pin "13") (pinfunction "G_13") (pintype "input"))
      (node (ref "IC2") (pin "8") (pinfunction "GND_8") (pintype "power_in"))
      (node (ref "IC3") (pin "2") (pinfunction "A_2") (pintype "passive"))
      (node (ref "IC4") (pin "12") (pinfunction "AGND_12") (pintype "bidirectional"))
      (node (ref "IC4") (pin "7") (pinfunction "DGND_7") (pintype "bidirectional"))
      (node (ref "IC5") (pin "8") (pinfunction "GND_8") (pintype "power_in"))
      (node (ref "IC6") (pin "1") (pinfunction "GND_1") (pintype "power_in"))
      (node (ref "IC7") (pin "10") (pinfunction "+IN_10") (pintype "input"))
      (node (ref "IC7") (pin "11") (pinfunction "V-_11") (pintype "power_in"))
      (node (ref "IC7") (pin "12") (pinfunction "+IN_12") (pintype "input"))
      (node (ref "IC7") (pin "3") (pinfunction "+IN_3") (pintype "input"))
      (node (ref "IC7") (pin "5") (pinfunction "+IN_5") (pintype "input"))
      (node (ref "IC8") (pin "1") (pinfunction "C_1") (pintype "passive"))
      (node (ref "IC9") (pin "10") (pinfunction "+IN_10") (pintype "input"))
      (node (ref "IC9") (pin "12") (pinfunction "+IN_12") (pintype "input"))
      (node (ref "IC9") (pin "3") (pinfunction "+IN_3") (pintype "input"))
      (node (ref "IC9") (pin "5") (pinfunction "+IN_5") (pintype "input"))
      (node (ref "J1") (pin "P1") (pinfunction "1_P1") (pintype "passive"))
      (node (ref "J2") (pin "P1") (pinfunction "1_P1") (pintype "passive"))
      (node (ref "J3") (pin "P1") (pinfunction "1_P1") (pintype "passive"))
      (node (ref "J4") (pin "P1") (pinfunction "1_P1") (pintype "passive"))
      (node (ref "J5") (pin "P1") (pinfunction "1_P1") (pintype "passive"))
      (node (ref "J6") (pin "P1") (pinfunction "1_P1") (pintype "passive"))
      (node (ref "JP1") (pin "3") (pinfunction "3_3") (pintype "passive"))
      (node (ref "JP1") (pin "4") (pinfunction "4_4") (pintype "passive"))
      (node (ref "JP1") (pin "5") (pinfunction "5_5") (pintype "passive"))
      (node (ref "JP1") (pin "6") (pinfunction "6_6") (pintype "passive"))
      (node (ref "JP1") (pin "7") (pinfunction "7_7") (pintype "passive"))
      (node (ref "JP1") (pin "8") (pinfunction "8_8") (pintype "passive"))
      (node (ref "JP2") (pin "3") (pinfunction "3_3") (pintype "passive"))
      (node (ref "JP2") (pin "5") (pinfunction "5_5") (pintype "passive"))
      (node (ref "JP2") (pin "9") (pinfunction "9_9") (pintype "passive"))
      (node (ref "JP3") (pin "1") (pinfunction "1_1") (pintype "passive"))
      (node (ref "Q1") (pin "E") (pinfunction "E_E") (pintype "passive"))
      (node (ref "Q2") (pin "E") (pinfunction "E_E") (pintype "passive"))
      (node (ref "Q3") (pin "E") (pinfunction "E_E") (pintype "passive"))
      (node (ref "Q4") (pin "E") (pinfunction "E_E") (pintype "passive"))
      (node (ref "Q6") (pin "E") (pinfunction "E_E") (pintype "passive"))
      (node (ref "R19") (pin "P$3") (pinfunction "A_P$3") (pintype "passive"))
      (node (ref "R20") (pin "P$3") (pinfunction "A_P$3") (pintype "passive"))
      (node (ref "R33") (pin "1") (pinfunction "1_1") (pintype "passive"))
      (node (ref "R36") (pin "P$3") (pinfunction "A_P$3") (pintype "passive"))
      (node (ref "R38") (pin "P$3") (pinfunction "A_P$3") (pintype "passive"))
      (node (ref "SW1") (pin "C") (pinfunction "C_C") (pintype "passive"))
      (node (ref "SW1") (pin "D") (pinfunction "1_D") (pintype "passive"))
      (node (ref "SW2") (pin "A") (pinfunction "P_A") (pintype "passive"))
      (node (ref "SW2") (pin "A'") (pinfunction "P1_A'") (pintype "passive"))
      (node (ref "UC1") (pin "20") (pinfunction "PB2/BOOT1_20") (pintype "bidirectional"))
      (node (ref "UC1") (pin "23") (pinfunction "VSS_1_23") (pintype "power_in"))
      (node (ref "UC1") (pin "35") (pinfunction "VSS_2_35") (pintype "power_in"))
      (node (ref "UC1") (pin "46") (pinfunction "PB9/TIM4_CH4_46") (pintype "input"))
      (node (ref "UC1") (pin "47") (pinfunction "VSS_3_47") (pintype "power_in"))
      (node (ref "UC1") (pin "8") (pinfunction "VSS_A_8") (pintype "power_in"))
    )
    (net (code "27") (name "JTCK") (class "Default")
      (node (ref "JP2") (pin "4") (pinfunction "4_4") (pintype "passive"))
      (node (ref "UC1") (pin "37") (pinfunction "PA14/JTCK/SWCLK_37") (pintype "bidirectional"))
    )
    (net (code "28") (name "JTDI") (class "Default")
      (node (ref "JP2") (pin "8") (pinfunction "8_8") (pintype "passive"))
      (node (ref "UC1") (pin "38") (pinfunction "PA15/JTDI_38") (pintype "bidirectional"))
    )
    (net (code "29") (name "JTDO") (class "Default")
      (node (ref "JP2") (pin "6") (pinfunction "6_6") (pintype "passive"))
      (node (ref "UC1") (pin "39") (pinfunction "PB3/JTDO_39") (pintype "bidirectional"))
    )
    (net (code "30") (name "JTMS") (class "Default")
      (node (ref "JP2") (pin "2") (pinfunction "2_2") (pintype "passive"))
      (node (ref "UC1") (pin "34") (pinfunction "PA13/JTMS/SWDIO_34") (pintype "bidirectional"))
    )
    (net (code "31") (name "Net-(C21-Pad1)") (class "Default")
      (node (ref "C21") (pin "1") (pinfunction "1_1") (pintype "passive"))
      (node (ref "R45") (pin "1") (pinfunction "1_1") (pintype "passive"))
      (node (ref "R46") (pin "2") (pinfunction "2_2") (pintype "passive"))
    )
    (net (code "32") (name "Net-(C24-Pad-)") (class "Default")
      (node (ref "C24") (pin "-") (pinfunction "-_-") (pintype "passive"))
      (node (ref "R50") (pin "2") (pinfunction "2_2") (pintype "passive"))
    )
    (net (code "33") (name "Net-(D1-PadA)") (class "Default")
      (node (ref "D1") (pin "A") (pinfunction "A_A") (pintype "passive"))
      (node (ref "JP1") (pin "1") (pinfunction "1_1") (pintype "passive"))
      (node (ref "JP1") (pin "2") (pinfunction "2_2") (pintype "passive"))
    )
    (net (code "34") (name "Net-(D2-PadC)") (class "Default")
      (node (ref "D2") (pin "C") (pinfunction "C_C") (pintype "passive"))
      (node (ref "JP1") (pin "10") (pinfunction "10_10") (pintype "passive"))
      (node (ref "JP1") (pin "9") (pinfunction "9_9") (pintype "passive"))
    )
    (net (code "35") (name "Net-(DISP1-A)") (class "Default")
      (node (ref "DISP1") (pin "12") (pinfunction "A_12") (pintype "passive"))
      (node (ref "DISP2") (pin "12") (pinfunction "A_12") (pintype "passive"))
      (node (ref "R9") (pin "2") (pinfunction "2_2") (pintype "passive"))
    )
    (net (code "36") (name "Net-(DISP1-B)") (class "Default")
      (node (ref "DISP1") (pin "10") (pinfunction "B_10") (pintype "passive"))
      (node (ref "DISP2") (pin "10") (pinfunction "B_10") (pintype "passive"))
      (node (ref "R10") (pin "2") (pinfunction "2_2") (pintype "passive"))
    )
    (net (code "37") (name "Net-(DISP1-C)") (class "Default")
      (node (ref "DISP1") (pin "9") (pinfunction "C_9") (pintype "passive"))
      (node (ref "DISP2") (pin "9") (pinfunction "C_9") (pintype "passive"))
      (node (ref "R12") (pin "2") (pinfunction "2_2") (pintype "passive"))
    )
    (net (code "38") (name "Net-(DISP1-D)") (class "Default")
      (node (ref "DISP1") (pin "7") (pinfunction "D_7") (pintype "passive"))
      (node (ref "DISP2") (pin "7") (pinfunction "D_7") (pintype "passive"))
      (node (ref "R18") (pin "2") (pinfunction "2_2") (pintype "passive"))
    )
    (net (code "39") (name "Net-(DISP1-E)") (class "Default")
      (node (ref "DISP1") (pin "1") (pinfunction "E_1") (pintype "passive"))
      (node (ref "DISP2") (pin "1") (pinfunction "E_1") (pintype "passive"))
      (node (ref "R13") (pin "2") (pinfunction "2_2") (pintype "passive"))
    )
    (net (code "40") (name "Net-(DISP1-F)") (class "Default")
      (node (ref "DISP1") (pin "18") (pinfunction "F_18") (pintype "passive"))
      (node (ref "DISP2") (pin "18") (pinfunction "F_18") (pintype "passive"))
      (node (ref "R4") (pin "2") (pinfunction "2_2") (pintype "passive"))
    )
    (net (code "41") (name "Net-(DISP1-G)") (class "Default")
      (node (ref "DISP1") (pin "17") (pinfunction "G_17") (pintype "passive"))
      (node (ref "DISP2") (pin "17") (pinfunction "G_17") (pintype "passive"))
      (node (ref "R5") (pin "2") (pinfunction "2_2") (pintype "passive"))
    )
    (net (code "42") (name "Net-(DISP1-H)") (class "Default")
      (node (ref "DISP1") (pin "15") (pinfunction "H_15") (pintype "passive"))
      (node (ref "DISP2") (pin "15") (pinfunction "H_15") (pintype "passive"))
      (node (ref "R6") (pin "2") (pinfunction "2_2") (pintype "passive"))
    )
    (net (code "43") (name "Net-(DISP1-J)") (class "Default")
      (node (ref "DISP1") (pin "14") (pinfunction "J_14") (pintype "passive"))
      (node (ref "DISP2") (pin "14") (pinfunction "J_14") (pintype "passive"))
      (node (ref "R7") (pin "2") (pinfunction "2_2") (pintype "passive"))
    )
    (net (code "44") (name "Net-(DISP1-K)") (class "Default")
      (node (ref "DISP1") (pin "6") (pinfunction "K_6") (pintype "passive"))
      (node (ref "DISP2") (pin "6") (pinfunction "K_6") (pintype "passive"))
      (node (ref "R17") (pin "2") (pinfunction "2_2") (pintype "passive"))
    )
    (net (code "45") (name "Net-(DISP1-K1)") (class "Default")
      (node (ref "DISP1") (pin "16") (pinfunction "K1_16") (pintype "passive"))
      (node (ref "Q1") (pin "C") (pinfunction "C_C") (pintype "passive"))
    )
    (net (code "46") (name "Net-(DISP1-K2)") (class "Default")
      (node (ref "DISP1") (pin "11") (pinfunction "K2_11") (pintype "passive"))
      (node (ref "Q2") (pin "C") (pinfunction "C_C") (pintype "passive"))
    )
    (net (code "47") (name "Net-(DISP1-L)") (class "Default")
      (node (ref "DISP1") (pin "5") (pinfunction "L_5") (pintype "passive"))
      (node (ref "DISP2") (pin "5") (pinfunction "L_5") (pintype "passive"))
      (node (ref "R16") (pin "2") (pinfunction "2_2") (pintype "passive"))
    )
    (net (code "48") (name "Net-(DISP1-M)") (class "Default")
      (node (ref "DISP1") (pin "4") (pinfunction "M_4") (pintype "passive"))
      (node (ref "DISP2") (pin "4") (pinfunction "M_4") (pintype "passive"))
      (node (ref "R15") (pin "2") (pinfunction "2_2") (pintype "passive"))
    )
    (net (code "49") (name "Net-(DISP1-N)") (class "Default")
      (node (ref "DISP1") (pin "2") (pinfunction "N_2") (pintype "passive"))
      (node (ref "DISP2") (pin "2") (pinfunction "N_2") (pintype "passive"))
      (node (ref "R14") (pin "2") (pinfunction "2_2") (pintype "passive"))
    )
    (net (code "50") (name "Net-(DISP1-P)") (class "Default")
      (node (ref "DISP1") (pin "13") (pinfunction "P_13") (pintype "passive"))
      (node (ref "DISP2") (pin "13") (pinfunction "P_13") (pintype "passive"))
      (node (ref "R8") (pin "2") (pinfunction "2_2") (pintype "passive"))
    )
    (net (code "51") (name "Net-(DISP2-K1)") (class "Default")
      (node (ref "DISP2") (pin "16") (pinfunction "K1_16") (pintype "passive"))
      (node (ref "Q3") (pin "C") (pinfunction "C_C") (pintype "passive"))
    )
    (net (code "52") (name "Net-(DISP2-K2)") (class "Default")
      (node (ref "DISP2") (pin "11") (pinfunction "K2_11") (pintype "passive"))
      (node (ref "Q4") (pin "C") (pinfunction "C_C") (pintype "passive"))
    )
    (net (code "53") (name "Net-(IC1A-QA)") (class "Default")
      (node (ref "IC1") (pin "15") (pinfunction "QA_15") (pintype "tri_state"))
      (node (ref "R7") (pin "1") (pinfunction "1_1") (pintype "passive"))
    )
    (net (code "54") (name "Net-(IC1A-QB)") (class "Default")
      (node (ref "IC1") (pin "1") (pinfunction "QB_1") (pintype "tri_state"))
      (node (ref "R17") (pin "1") (pinfunction "1_1") (pintype "passive"))
    )
    (net (code "55") (name "Net-(IC1A-QC)") (class "Default")
      (node (ref "IC1") (pin "2") (pinfunction "QC_2") (pintype "tri_state"))
      (node (ref "R16") (pin "1") (pinfunction "1_1") (pintype "passive"))
    )
    (net (code "56") (name "Net-(IC1A-QD)") (class "Default")
      (node (ref "IC1") (pin "3") (pinfunction "QD_3") (pintype "tri_state"))
      (node (ref "R15") (pin "1") (pinfunction "1_1") (pintype "passive"))
    )
    (net (code "57") (name "Net-(IC1A-QE)") (class "Default")
      (node (ref "IC1") (pin "4") (pinfunction "QE_4") (pintype "tri_state"))
      (node (ref "R14") (pin "1") (pinfunction "1_1") (pintype "passive"))
    )
    (net (code "58") (name "Net-(IC1A-QF)") (class "Default")
      (node (ref "IC1") (pin "5") (pinfunction "QF_5") (pintype "tri_state"))
      (node (ref "R8") (pin "1") (pinfunction "1_1") (pintype "passive"))
    )
    (net (code "59") (name "Net-(IC1A-SER)") (class "Default")
      (node (ref "IC1") (pin "14") (pinfunction "SER_14") (pintype "input"))
      (node (ref "IC2") (pin "9") (pinfunction "QH*_9") (pintype "tri_state"))
    )
    (net (code "60") (name "Net-(IC2A-QA)") (class "Default")
      (node (ref "IC2") (pin "15") (pinfunction "QA_15") (pintype "tri_state"))
      (node (ref "R9") (pin "1") (pinfunction "1_1") (pintype "passive"))
    )
    (net (code "61") (name "Net-(IC2A-QB)") (class "Default")
      (node (ref "IC2") (pin "1") (pinfunction "QB_1") (pintype "tri_state"))
      (node (ref "R10") (pin "1") (pinfunction "1_1") (pintype "passive"))
    )
    (net (code "62") (name "Net-(IC2A-QC)") (class "Default")
      (node (ref "IC2") (pin "2") (pinfunction "QC_2") (pintype "tri_state"))
      (node (ref "R12") (pin "1") (pinfunction "1_1") (pintype "passive"))
    )
    (net (code "63") (name "Net-(IC2A-QD)") (class "Default")
      (node (ref "IC2") (pin "3") (pinfunction "QD_3") (pintype "tri_state"))
      (node (ref "R18") (pin "1") (pinfunction "1_1") (pintype "passive"))
    )
    (net (code "64") (name "Net-(IC2A-QE)") (class "Default")
      (node (ref "IC2") (pin "4") (pinfunction "QE_4") (pintype "tri_state"))
      (node (ref "R13") (pin "1") (pinfunction "1_1") (pintype "passive"))
    )
    (net (code "65") (name "Net-(IC2A-QF)") (class "Default")
      (node (ref "IC2") (pin "5") (pinfunction "QF_5") (pintype "tri_state"))
      (node (ref "R4") (pin "1") (pinfunction "1_1") (pintype "passive"))
    )
    (net (code "66") (name "Net-(IC2A-QG)") (class "Default")
      (node (ref "IC2") (pin "6") (pinfunction "QG_6") (pintype "tri_state"))
      (node (ref "R5") (pin "1") (pinfunction "1_1") (pintype "passive"))
    )
    (net (code "67") (name "Net-(IC2A-QH)") (class "Default")
      (node (ref "IC2") (pin "7") (pinfunction "QH_7") (pintype "tri_state"))
      (node (ref "R6") (pin "1") (pinfunction "1_1") (pintype "passive"))
    )
    (net (code "68") (name "Net-(IC6-VIN)") (class "Default")
      (node (ref "C19") (pin "+") (pinfunction "+_+") (pintype "passive"))
      (node (ref "IC6") (pin "2") (pinfunction "VIN_2") (pintype "input"))
      (node (ref "R49") (pin "1") (pinfunction "1_1") (pintype "passive"))
    )
    (net (code "69") (name "Net-(IC7A--IN)") (class "Default")
      (node (ref "C16") (pin "1") (pinfunction "1_1") (pintype "passive"))
      (node (ref "IC7") (pin "2") (pinfunction "-IN_2") (pintype "input"))
      (node (ref "R34") (pin "1") (pinfunction "1_1") (pintype "passive"))
      (node (ref "R39") (pin "2") (pinfunction "2_2") (pintype "passive"))
      (node (ref "R41") (pin "2") (pinfunction "2_2") (pintype "passive"))
    )
    (net (code "70") (name "Net-(IC7B--IN)") (class "Default")
      (node (ref "C17") (pin "1") (pinfunction "1_1") (pintype "passive"))
      (node (ref "IC7") (pin "6") (pinfunction "-IN_6") (pintype "input"))
      (node (ref "R21") (pin "P$3") (pinfunction "A_P$3") (pintype "passive"))
      (node (ref "R35") (pin "1") (pinfunction "1_1") (pintype "passive"))
      (node (ref "R40") (pin "2") (pinfunction "2_2") (pintype "passive"))
      (node (ref "R42") (pin "2") (pinfunction "2_2") (pintype "passive"))
    )
    (net (code "71") (name "Net-(IC7C--IN)") (class "Default")
      (node (ref "C14") (pin "1") (pinfunction "1_1") (pintype "passive"))
      (node (ref "IC7") (pin "9") (pinfunction "-IN_9") (pintype "input"))
      (node (ref "R26") (pin "1") (pinfunction "1_1") (pintype "passive"))
      (node (ref "R31") (pin "2") (pinfunction "2_2") (pintype "passive"))
      (node (ref "R32") (pin "2") (pinfunction "2_2") (pintype "passive"))
    )
    (net (code "72") (name "Net-(IC7D--IN)") (class "Default")
      (node (ref "C13") (pin "1") (pinfunction "1_1") (pintype "passive"))
      (node (ref "IC7") (pin "13") (pinfunction "-IN_13") (pintype "input"))
      (node (ref "R25") (pin "1") (pinfunction "1_1") (pintype "passive"))
      (node (ref "R28") (pin "2") (pinfunction "2_2") (pintype "passive"))
      (node (ref "R30") (pin "2") (pinfunction "2_2") (pintype "passive"))
      (node (ref "R37") (pin "P$3") (pinfunction "A_P$3") (pintype "passive"))
    )
    (net (code "73") (name "Net-(IC9A--IN)") (class "Default")
      (node (ref "IC9") (pin "2") (pinfunction "-IN_2") (pintype "input"))
      (node (ref "R21") (pin "P$1") (pinfunction "E_P$1") (pintype "passive"))
      (node (ref "R52") (pin "1") (pinfunction "1_1") (pintype "passive"))
    )
    (net (code "74") (name "Net-(IC9A-OUT)") (class "Default")
      (node (ref "IC9") (pin "1") (pinfunction "OUT_1") (pintype "output"))
      (node (ref "R42") (pin "1") (pinfunction "1_1") (pintype "passive"))
      (node (ref "R52") (pin "2") (pinfunction "2_2") (pintype "passive"))
    )
    (net (code "75") (name "Net-(IC9B--IN)") (class "Default")
      (node (ref "IC9") (pin "6") (pinfunction "-IN_6") (pintype "input"))
      (node (ref "R53") (pin "1") (pinfunction "1_1") (pintype "passive"))
      (node (ref "R54") (pin "2") (pinfunction "2_2") (pintype "passive"))
    )
    (net (code "76") (name "Net-(IC9B-OUT)") (class "Default")
      (node (ref "IC9") (pin "7") (pinfunction "OUT_7") (pintype "output"))
      (node (ref "R41") (pin "1") (pinfunction "1_1") (pintype "passive"))
      (node (ref "R53") (pin "2") (pinfunction "2_2") (pintype "passive"))
    )
    (net (code "77") (name "Net-(IC9C--IN)") (class "Default")
      (node (ref "IC9") (pin "9") (pinfunction "-IN_9") (pintype "input"))
      (node (ref "R44") (pin "1") (pinfunction "1_1") (pintype "passive"))
      (node (ref "R47") (pin "2") (pinfunction "2_2") (pintype "passive"))
    )
    (net (code "78") (name "Net-(IC9C-OUT)") (class "Default")
      (node (ref "IC9") (pin "8") (pinfunction "OUT_8") (pintype "output"))
      (node (ref "R31") (pin "1") (pinfunction "1_1") (pintype "passive"))
      (node (ref "R44") (pin "2") (pinfunction "2_2") (pintype "passive"))
    )
    (net (code "79") (name "Net-(IC9D--IN)") (class "Default")
      (node (ref "IC9") (pin "13") (pinfunction "-IN_13") (pintype "input"))
      (node (ref "R37") (pin "P$1") (pinfunction "E_P$1") (pintype "passive"))
      (node (ref "R43") (pin "1") (pinfunction "1_1") (pintype "passive"))
    )
    (net (code "80") (name "Net-(IC9D-OUT)") (class "Default")
      (node (ref "IC9") (pin "14") (pinfunction "OUT_14") (pintype "output"))
      (node (ref "R30") (pin "1") (pinfunction "1_1") (pintype "passive"))
      (node (ref "R43") (pin "2") (pinfunction "2_2") (pintype "passive"))
    )
    (net (code "81") (name "Net-(IC10A--IN)") (class "Default")
      (node (ref "C29") (pin "1") (pinfunction "1_1") (pintype "passive"))
      (node (ref "IC10") (pin "2") (pinfunction "-IN_2") (pintype "input"))
      (node (ref "R50") (pin "1") (pinfunction "1_1") (pintype "passive"))
      (node (ref "R56") (pin "2") (pinfunction "2_2") (pintype "passive"))
    )
    (net (code "82") (name "Net-(IC10A-OUT)") (class "Default")
      (node (ref "C29") (pin "2") (pinfunction "2_2") (pintype "passive"))
      (node (ref "IC10") (pin "1") (pinfunction "OUT_1") (pintype "output"))
      (node (ref "R55") (pin "2") (pinfunction "2_2") (pintype "passive"))
    )
    (net (code "83") (name "Net-(IC10B-+IN)") (class "Default")
      (node (ref "C22") (pin "1") (pinfunction "1_1") (pintype "passive"))
      (node (ref "IC10") (pin "5") (pinfunction "+IN_5") (pintype "input"))
      (node (ref "R46") (pin "1") (pinfunction "1_1") (pintype "passive"))
    )
    (net (code "84") (name "Net-(IC10B--IN)") (class "Default")
      (node (ref "C21") (pin "2") (pinfunction "2_2") (pintype "passive"))
      (node (ref "C24") (pin "+") (pinfunction "+_+") (pintype "passive"))
      (node (ref "IC10") (pin "6") (pinfunction "-IN_6") (pintype "input"))
      (node (ref "IC10") (pin "7") (pinfunction "OUT_7") (pintype "output"))
    )
    (net (code "85") (name "Net-(J1-3)") (class "Default")
      (node (ref "J1") (pin "P3") (pinfunction "3_P3") (pintype "passive"))
      (node (ref "R29") (pin "1") (pinfunction "1_1") (pintype "passive"))
    )
    (net (code "86") (name "Net-(J2-3)") (class "Default")
      (node (ref "J2") (pin "P3") (pinfunction "3_P3") (pintype "passive"))
      (node (ref "R54") (pin "1") (pinfunction "1_1") (pintype "passive"))
    )
    (net (code "87") (name "Net-(J3-3)") (class "Default")
      (node (ref "J3") (pin "P3") (pinfunction "3_P3") (pintype "passive"))
      (node (ref "R24") (pin "1") (pinfunction "1_1") (pintype "passive"))
    )
    (net (code "88") (name "Net-(J4-3)") (class "Default")
      (node (ref "J4") (pin "P3") (pinfunction "3_P3") (pintype "passive"))
      (node (ref "R48") (pin "1") (pinfunction "1_1") (pintype "passive"))
    )
    (net (code "89") (name "Net-(J5-3)") (class "Default")
      (node (ref "J5") (pin "P3") (pinfunction "3_P3") (pintype "passive"))
      (node (ref "R47") (pin "1") (pinfunction "1_1") (pintype "passive"))
    )
    (net (code "90") (name "Net-(J6-3)") (class "Default")
      (node (ref "J6") (pin "P3") (pinfunction "3_P3") (pintype "passive"))
      (node (ref "R55") (pin "1") (pinfunction "1_1") (pintype "passive"))
      (node (ref "R56") (pin "1") (pinfunction "1_1") (pintype "passive"))
    )
    (net (code "91") (name "Net-(Q1-PadB)") (class "Default")
      (node (ref "Q1") (pin "B") (pinfunction "B_B") (pintype "passive"))
      (node (ref "R1") (pin "2") (pinfunction "2_2") (pintype "passive"))
    )
    (net (code "92") (name "Net-(Q2-PadB)") (class "Default")
      (node (ref "Q2") (pin "B") (pinfunction "B_B") (pintype "passive"))
      (node (ref "R2") (pin "2") (pinfunction "2_2") (pintype "passive"))
    )
    (net (code "93") (name "Net-(Q3-PadB)") (class "Default")
      (node (ref "Q3") (pin "B") (pinfunction "B_B") (pintype "passive"))
      (node (ref "R3") (pin "2") (pinfunction "2_2") (pintype "passive"))
    )
    (net (code "94") (name "Net-(Q4-PadB)") (class "Default")
      (node (ref "Q4") (pin "B") (pinfunction "B_B") (pintype "passive"))
      (node (ref "R11") (pin "2") (pinfunction "2_2") (pintype "passive"))
    )
    (net (code "95") (name "Net-(Q6-PadB)") (class "Default")
      (node (ref "Q6") (pin "B") (pinfunction "B_B") (pintype "passive"))
      (node (ref "R29") (pin "2") (pinfunction "2_2") (pintype "passive"))
    )
    (net (code "96") (name "Net-(R20-S)") (class "Default")
      (node (ref "R20") (pin "P$2") (pinfunction "S_P$2") (pintype "passive"))
      (node (ref "R39") (pin "1") (pinfunction "1_1") (pintype "passive"))
    )
    (net (code "97") (name "Net-(R21-S)") (class "Default")
      (node (ref "R21") (pin "P$2") (pinfunction "S_P$2") (pintype "passive"))
      (node (ref "R24") (pin "2") (pinfunction "2_2") (pintype "passive"))
    )
    (net (code "98") (name "Net-(R36-S)") (class "Default")
      (node (ref "R28") (pin "1") (pinfunction "1_1") (pintype "passive"))
      (node (ref "R36") (pin "P$2") (pinfunction "S_P$2") (pintype "passive"))
    )
    (net (code "99") (name "Net-(R37-S)") (class "Default")
      (node (ref "R37") (pin "P$2") (pinfunction "S_P$2") (pintype "passive"))
      (node (ref "R48") (pin "2") (pinfunction "2_2") (pintype "passive"))
    )
    (net (code "100") (name "Net-(R38-S)") (class "Default")
      (node (ref "R32") (pin "1") (pinfunction "1_1") (pintype "passive"))
      (node (ref "R38") (pin "P$2") (pinfunction "S_P$2") (pintype "passive"))
    )
    (net (code "101") (name "Net-(UC1-PD0-OSC_IN)") (class "Default")
      (node (ref "C9") (pin "2") (pinfunction "2_2") (pintype "passive"))
      (node (ref "Q5") (pin "2") (pinfunction "2_2") (pintype "passive"))
      (node (ref "UC1") (pin "5") (pinfunction "PD0-OSC_IN_5") (pintype "input"))
    )
    (net (code "102") (name "Net-(UC1-PD1-OSC_OUT)") (class "Default")
      (node (ref "C10") (pin "2") (pinfunction "2_2") (pintype "passive"))
      (node (ref "Q5") (pin "1") (pinfunction "1_1") (pintype "passive"))
      (node (ref "UC1") (pin "6") (pinfunction "PD1-OSC_OUT_6") (pintype "input"))
    )
    (net (code "103") (name "PARAM1_CV") (class "Default")
      (node (ref "C13") (pin "2") (pinfunction "2_2") (pintype "passive"))
      (node (ref "IC4") (pin "1") (pinfunction "CH0_1") (pintype "bidirectional"))
      (node (ref "IC7") (pin "14") (pinfunction "OUT_14") (pintype "output"))
      (node (ref "R25") (pin "2") (pinfunction "2_2") (pintype "passive"))
    )
    (net (code "104") (name "PARAM2_CV") (class "Default")
      (node (ref "C14") (pin "2") (pinfunction "2_2") (pintype "passive"))
      (node (ref "IC4") (pin "2") (pinfunction "CH1_2") (pintype "bidirectional"))
      (node (ref "IC7") (pin "8") (pinfunction "OUT_8") (pintype "output"))
      (node (ref "R26") (pin "2") (pinfunction "2_2") (pintype "passive"))
    )
    (net (code "105") (name "PITCH_CV") (class "Default")
      (node (ref "C16") (pin "2") (pinfunction "2_2") (pintype "passive"))
      (node (ref "IC4") (pin "3") (pinfunction "CH2_3") (pintype "bidirectional"))
      (node (ref "IC7") (pin "1") (pinfunction "OUT_1") (pintype "output"))
      (node (ref "R34") (pin "2") (pinfunction "2_2") (pintype "passive"))
    )
    (net (code "106") (name "RESET") (class "Default")
      (node (ref "JP2") (pin "10") (pinfunction "10_10") (pintype "passive"))
      (node (ref "R22") (pin "1") (pinfunction "1_1") (pintype "passive"))
      (node (ref "SW2") (pin "B") (pinfunction "S_B") (pintype "passive"))
      (node (ref "SW2") (pin "B'") (pinfunction "S1_B'") (pintype "passive"))
      (node (ref "UC1") (pin "7") (pinfunction "NRST_7") (pintype "input"))
    )
    (net (code "107") (name "RX") (class "Default")
      (node (ref "JP3") (pin "4") (pinfunction "4_4") (pintype "passive"))
      (node (ref "UC1") (pin "31") (pinfunction "PA10/USART1_RX/TIM1_CH3_31") (pintype "bidirectional"))
    )
    (net (code "108") (name "TX") (class "Default")
      (node (ref "JP3") (pin "5") (pinfunction "5_5") (pintype "passive"))
      (node (ref "UC1") (pin "30") (pinfunction "PA9/USART1_TX/TIM1_CH2_30") (pintype "input"))
    )
    (net (code "109") (name "VCC") (class "Default")
      (node (ref "C23") (pin "1") (pinfunction "1_1") (pintype "passive"))
      (node (ref "C25") (pin "+") (pinfunction "+_+") (pintype "passive"))
      (node (ref "C28") (pin "1") (pinfunction "1_1") (pintype "passive"))
      (node (ref "D1") (pin "C") (pinfunction "C_C") (pintype "passive"))
      (node (ref "IC10") (pin "8") (pinfunction "V+_8") (pintype "power_in"))
      (node (ref "IC9") (pin "4") (pinfunction "V+_4") (pintype "power_in"))
      (node (ref "R49") (pin "2") (pinfunction "2_2") (pintype "passive"))
    )
    (net (code "110") (name "VEE") (class "Default")
      (node (ref "C20") (pin "2") (pinfunction "2_2") (pintype "passive"))
      (node (ref "C27") (pin "2") (pinfunction "2_2") (pintype "passive"))
      (node (ref "C30") (pin "-") (pinfunction "-_-") (pintype "passive"))
      (node (ref "D2") (pin "A") (pinfunction "A_A") (pintype "passive"))
      (node (ref "IC10") (pin "4") (pinfunction "V-_4") (pintype "power_in"))
      (node (ref "IC9") (pin "11") (pinfunction "V-_11") (pintype "power_in"))
      (node (ref "R51") (pin "1") (pinfunction "1_1") (pintype "passive"))
    )
    (net (code "111") (name "unconnected-(DISP1-DP-Pad8)") (class "Default")
      (node (ref "DISP1") (pin "8") (pinfunction "DP_8") (pintype "passive"))
    )
    (net (code "112") (name "unconnected-(DISP2-DP-Pad8)") (class "Default")
      (node (ref "DISP2") (pin "8") (pinfunction "DP_8") (pintype "passive"))
    )
    (net (code "113") (name "unconnected-(IC1A-QG-Pad6)") (class "Default")
      (node (ref "IC1") (pin "6") (pinfunction "QG_6") (pintype "tri_state"))
    )
    (net (code "114") (name "unconnected-(IC1A-QH*-Pad9)") (class "Default")
      (node (ref "IC1") (pin "9") (pinfunction "QH*_9") (pintype "tri_state"))
    )
    (net (code "115") (name "unconnected-(IC1A-QH-Pad7)") (class "Default")
      (node (ref "IC1") (pin "7") (pinfunction "QH_7") (pintype "tri_state"))
    )
    (net (code "116") (name "unconnected-(J1-2-PadP2)") (class "Default")
      (node (ref "J1") (pin "P2") (pinfunction "2_P2") (pintype "passive"))
    )
    (net (code "117") (name "unconnected-(J2-2-PadP2)") (class "Default")
      (node (ref "J2") (pin "P2") (pinfunction "2_P2") (pintype "passive"))
    )
    (net (code "118") (name "unconnected-(J3-2-PadP2)") (class "Default")
      (node (ref "J3") (pin "P2") (pinfunction "2_P2") (pintype "passive"))
    )
    (net (code "119") (name "unconnected-(J4-2-PadP2)") (class "Default")
      (node (ref "J4") (pin "P2") (pinfunction "2_P2") (pintype "passive"))
    )
    (net (code "120") (name "unconnected-(J5-2-PadP2)") (class "Default")
      (node (ref "J5") (pin "P2") (pinfunction "2_P2") (pintype "passive"))
    )
    (net (code "121") (name "unconnected-(J6-2-PadP2)") (class "Default")
      (node (ref "J6") (pin "P2") (pinfunction "2_P2") (pintype "passive"))
    )
    (net (code "122") (name "unconnected-(JP2-Pad7)") (class "Default")
      (node (ref "JP2") (pin "7") (pinfunction "7_7") (pintype "passive"))
    )
    (net (code "123") (name "unconnected-(JP3-Pad2)") (class "Default")
      (node (ref "JP3") (pin "2") (pinfunction "2_2") (pintype "passive"))
    )
    (net (code "124") (name "unconnected-(JP3-Pad3)") (class "Default")
      (node (ref "JP3") (pin "3") (pinfunction "3_3") (pintype "passive"))
    )
    (net (code "125") (name "unconnected-(JP3-Pad6)") (class "Default")
      (node (ref "JP3") (pin "6") (pinfunction "6_6") (pintype "passive"))
    )
    (net (code "126") (name "unconnected-(UC1-PA0_WKUP{slash}USART2_CTS{slash}ADC12_IN0{slash}TIM2_CH1_ETR-Pad10)") (class "Default")
      (node (ref "UC1") (pin "10") (pinfunction "PA0_WKUP/USART2_CTS/ADC12_IN0/TIM2_CH1_ETR_10") (pintype "bidirectional"))
    )
    (net (code "127") (name "unconnected-(UC1-PA1{slash}USART2_RTS{slash}ADC12_IN1{slash}TIM2_CH2-Pad11)") (class "Default")
      (node (ref "UC1") (pin "11") (pinfunction "PA1/USART2_RTS/ADC12_IN1/TIM2_CH2_11") (pintype "bidirectional"))
    )
    (net (code "128") (name "unconnected-(UC1-PA2{slash}USART2_TX{slash}ADC12_IN2{slash}TIM2_CH3-Pad12)") (class "Default")
      (node (ref "UC1") (pin "12") (pinfunction "PA2/USART2_TX/ADC12_IN2/TIM2_CH3_12") (pintype "bidirectional"))
    )
    (net (code "129") (name "unconnected-(UC1-PA8{slash}USART1_CK{slash}TIM1_CH1{slash}MCO-Pad29)") (class "Default")
      (node (ref "UC1") (pin "29") (pinfunction "PA8/USART1_CK/TIM1_CH1/MCO_29") (pintype "bidirectional"))
    )
    (net (code "130") (name "unconnected-(UC1-PA11{slash}USART1_CTS{slash}CAN_RX{slash}TIM1_CH4{slash}USBDM-Pad32)") (class "Default")
      (node (ref "UC1") (pin "32") (pinfunction "PA11/USART1_CTS/CAN_RX/TIM1_CH4/USBDM_32") (pintype "bidirectional"))
    )
    (net (code "131") (name "unconnected-(UC1-PA12{slash}USART1_RTS{slash}CAN_TX{slash}TIM1_ETR{slash}USBDP-Pad33)") (class "Default")
      (node (ref "UC1") (pin "33") (pinfunction "PA12/USART1_RTS/CAN_TX/TIM1_ETR/USBDP_33") (pintype "bidirectional"))
    )
    (net (code "132") (name "unconnected-(UC1-PB4{slash}NJTRST-Pad40)") (class "Default")
      (node (ref "UC1") (pin "40") (pinfunction "PB4/NJTRST_40") (pintype "bidirectional"))
    )
    (net (code "133") (name "unconnected-(UC1-PB14{slash}SPI2_MISO{slash}USART3_RTS{slash}TIM1_CH2N-Pad27)") (class "Default")
      (node (ref "UC1") (pin "27") (pinfunction "PB14/SPI2_MISO/USART3_RTS/TIM1_CH2N_27") (pintype "input"))
    )
  )
)
